# JLINK_V8_V1.net
KiCad netlist of a schematic drawn in Altium Designer
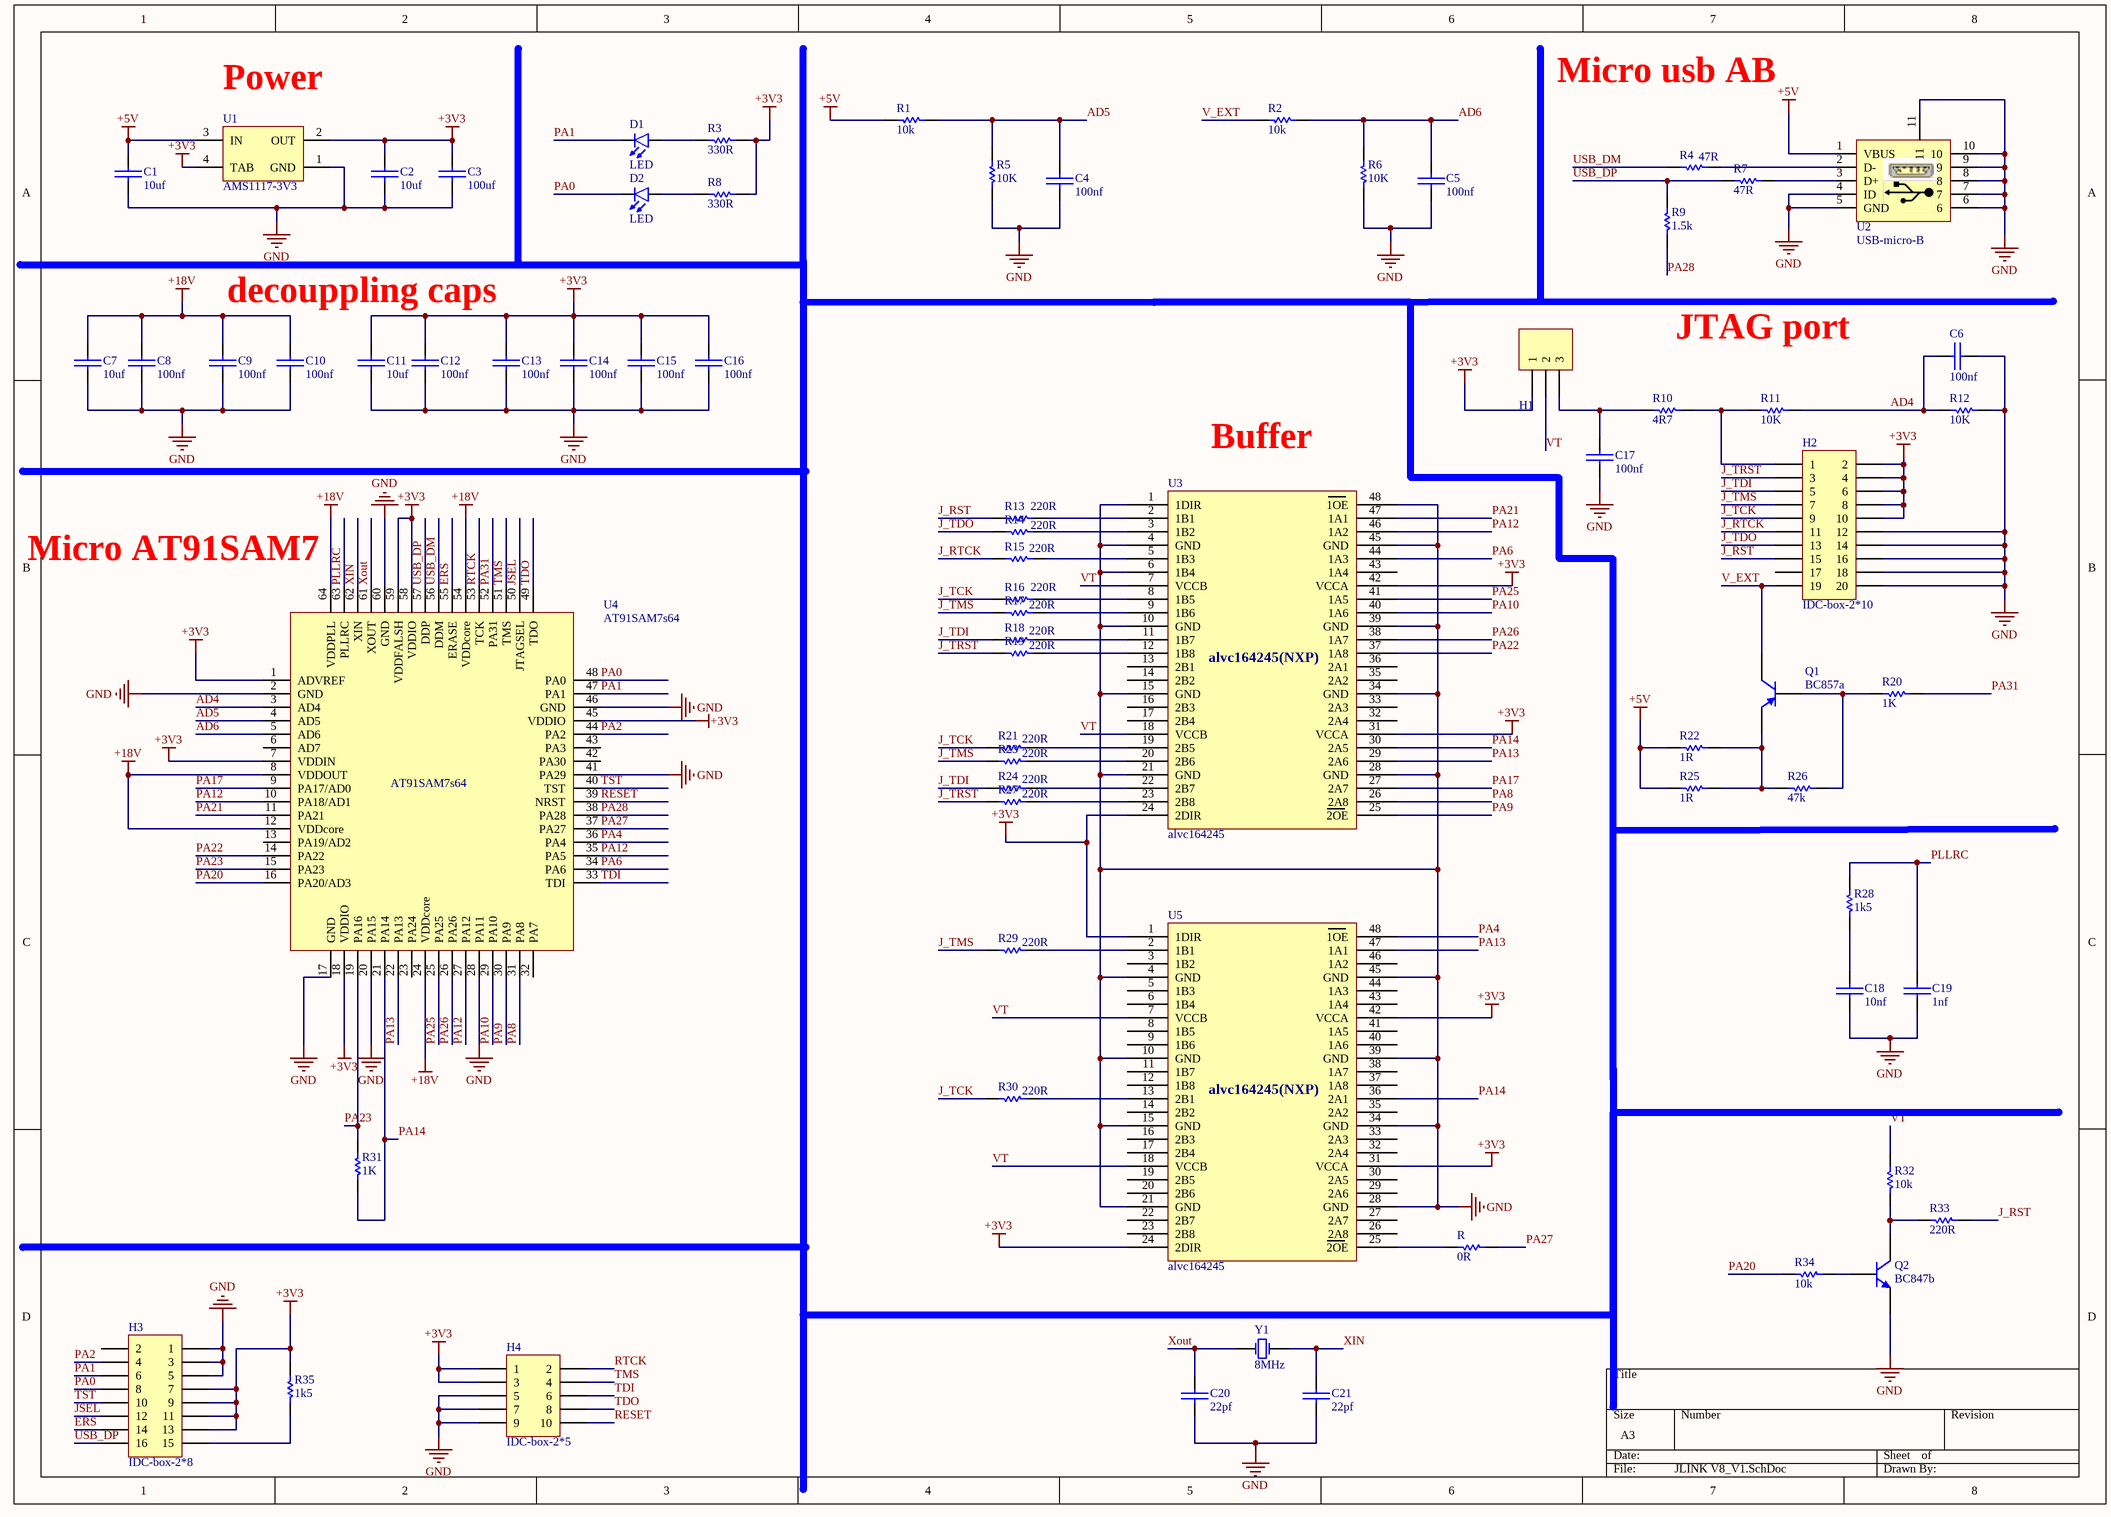
[diagram p0: JLINK V8_V1.SchDoc]

(export (version "E")
  (design (tool "Eeschema 10.0.6"))
  (components
    (comp (ref "C1")
      (value "10uf")
      (footprint "CAP-0805 - better")
      (libsource (lib "Pin_header32_Tester_V1") (part "CAP-0805"))
    )
    (comp (ref "C2")
      (value "10uf")
      (footprint "CAP-0805 - better")
      (libsource (lib "Pin_header32_Tester_V1") (part "CAP-0805"))
    )
    (comp (ref "C3")
      (value "100uf")
      (footprint "CAP-0805 - better")
      (libsource (lib "Pin_header32_Tester_V1") (part "CAP-0805"))
    )
    (comp (ref "C4")
      (value "100nf")
      (footprint "CAP-0805 - better")
      (libsource (lib "Pin_header32_Tester_V1") (part "CAP-0805"))
    )
    (comp (ref "C5")
      (value "100nf")
      (footprint "CAP-0805 - better")
      (libsource (lib "Pin_header32_Tester_V1") (part "CAP-0805"))
    )
    (comp (ref "C6")
      (value "100nf")
      (footprint "CAP-0805 - better")
      (libsource (lib "Pin_header32_Tester_V1") (part "CAP-0805"))
    )
    (comp (ref "C7")
      (value "10uf")
      (footprint "CAP-0805 - better")
      (libsource (lib "Pin_header32_Tester_V1") (part "CAP-0805"))
    )
    (comp (ref "C8")
      (value "100nf")
      (footprint "CAP-0805 - better")
      (libsource (lib "Pin_header32_Tester_V1") (part "CAP-0805"))
    )
    (comp (ref "C9")
      (value "100nf")
      (footprint "CAP-0805 - better")
      (libsource (lib "Pin_header32_Tester_V1") (part "CAP-0805"))
    )
    (comp (ref "C10")
      (value "100nf")
      (footprint "CAP-0805 - better")
      (libsource (lib "Pin_header32_Tester_V1") (part "CAP-0805"))
    )
    (comp (ref "C11")
      (value "10uf")
      (footprint "CAP-0805 - better")
      (libsource (lib "Pin_header32_Tester_V1") (part "CAP-0805"))
    )
    (comp (ref "C12")
      (value "100nf")
      (footprint "CAP-0805 - better")
      (libsource (lib "Pin_header32_Tester_V1") (part "CAP-0805"))
    )
    (comp (ref "C13")
      (value "100nf")
      (footprint "CAP-0805 - better")
      (libsource (lib "Pin_header32_Tester_V1") (part "CAP-0805"))
    )
    (comp (ref "C14")
      (value "100nf")
      (footprint "CAP-0805 - better")
      (libsource (lib "Pin_header32_Tester_V1") (part "CAP-0805"))
    )
    (comp (ref "C15")
      (value "100nf")
      (footprint "CAP-0805 - better")
      (libsource (lib "Pin_header32_Tester_V1") (part "CAP-0805"))
    )
    (comp (ref "C16")
      (value "100nf")
      (footprint "CAP-0805 - better")
      (libsource (lib "Pin_header32_Tester_V1") (part "CAP-0805"))
    )
    (comp (ref "C17")
      (value "100nf")
      (footprint "CAP-0805 - better")
      (libsource (lib "Pin_header32_Tester_V1") (part "CAP-0805"))
    )
    (comp (ref "C18")
      (value "10nf")
      (footprint "CAP-0805 - better")
      (libsource (lib "Pin_header32_Tester_V1") (part "CAP-0805"))
    )
    (comp (ref "C19")
      (value "1nf")
      (footprint "CAP-0805 - better")
      (libsource (lib "Pin_header32_Tester_V1") (part "CAP-0805"))
    )
    (comp (ref "C20")
      (value "22pf")
      (footprint "CAP-0805 - better")
      (libsource (lib "Pin_header32_Tester_V1") (part "CAP-0805"))
    )
    (comp (ref "C21")
      (value "22pf")
      (footprint "CAP-0805 - better")
      (libsource (lib "Pin_header32_Tester_V1") (part "CAP-0805"))
    )
    (comp (ref "D1")
      (value "LED")
      (footprint "LED-SMD-0805")
      (libsource (lib "Pin_header32_Tester_V1") (part "LED-SMD-RED"))
    )
    (comp (ref "D2")
      (value "LED")
      (footprint "LED-SMD-0805")
      (libsource (lib "Pin_header32_Tester_V1") (part "LED-SMD-RED"))
    )
    (comp (ref "H1")
      (value "Header 3")
      (footprint "PIN-header3(copy)")
      (description "Header, 3-Pin")
      (fields (field (name "PUBLISHER") "Altium Limited"))
      (libsource (lib "Pin_header32_Tester_V1") (part "Header 1*3"))
    )
    (comp (ref "H2")
      (value "IDC-box-2*10")
      (footprint "ICD-box_10*2")
      (libsource (lib "Pin_header32_Tester_V1") (part "Header 2*10"))
    )
    (comp (ref "H3")
      (value "IDC-box-2*8")
      (footprint "male-Header 2*8")
      (libsource (lib "Pin_header32_Tester_V1") (part "Header 2*8"))
    )
    (comp (ref "H4")
      (value "IDC-box-2*5")
      (footprint "male-Header-2*5 - duplicate")
      (description "Header, 5-Pin, Dual row")
      (fields (field (name "PUBLISHER") "Altium Limited"))
      (libsource (lib "Pin_header32_Tester_V1") (part "Header 2*5"))
    )
    (comp (ref "Q1")
      (value "BC857a")
      (footprint "sot23")
      (description "PNP Bipolar Transistor")
      (fields (field (name "PUBLISHER") "Altium Limited"))
      (libsource (lib "Pin_header32_Tester_V1") (part "PNP"))
    )
    (comp (ref "Q2")
      (value "BC847b")
      (footprint "sot23")
      (description "NPN Bipolar Transistor")
      (fields (field (name "PUBLISHER") "Altium Limited"))
      (libsource (lib "Pin_header32_Tester_V1") (part "NPN"))
    )
    (comp (ref "R")
      (value "0R")
      (footprint "Res_SMD_0805")
      (description "Resistor")
      (fields (field (name "PUBLISHER") "Altium Limited"))
      (libsource (lib "Pin_header32_Tester_V1") (part "Res"))
    )
    (comp (ref "R1")
      (value "10k")
      (footprint "Res_SMD_0805")
      (description "Resistor")
      (fields (field (name "PUBLISHER") "Altium Limited"))
      (libsource (lib "Pin_header32_Tester_V1") (part "Res"))
    )
    (comp (ref "R2")
      (value "10k")
      (footprint "Res_SMD_0805")
      (description "Resistor")
      (fields (field (name "PUBLISHER") "Altium Limited"))
      (libsource (lib "Pin_header32_Tester_V1") (part "Res"))
    )
    (comp (ref "R3")
      (value "330R")
      (footprint "Res_SMD_0805")
      (description "Resistor")
      (fields (field (name "PUBLISHER") "Altium Limited"))
      (libsource (lib "Pin_header32_Tester_V1") (part "Res"))
    )
    (comp (ref "R4")
      (value "47R")
      (footprint "Res_SMD_0805")
      (description "Resistor")
      (fields (field (name "PUBLISHER") "Altium Limited"))
      (libsource (lib "Pin_header32_Tester_V1") (part "Res"))
    )
    (comp (ref "R5")
      (value "10K")
      (footprint "Res_SMD_0805")
      (description "Resistor")
      (fields (field (name "PUBLISHER") "Altium Limited"))
      (libsource (lib "Pin_header32_Tester_V1") (part "Res"))
    )
    (comp (ref "R6")
      (value "10K")
      (footprint "Res_SMD_0805")
      (description "Resistor")
      (fields (field (name "PUBLISHER") "Altium Limited"))
      (libsource (lib "Pin_header32_Tester_V1") (part "Res"))
    )
    (comp (ref "R7")
      (value "47R")
      (footprint "Res_SMD_0805")
      (description "Resistor")
      (fields (field (name "PUBLISHER") "Altium Limited"))
      (libsource (lib "Pin_header32_Tester_V1") (part "Res"))
    )
    (comp (ref "R8")
      (value "330R")
      (footprint "Res_SMD_0805")
      (description "Resistor")
      (fields (field (name "PUBLISHER") "Altium Limited"))
      (libsource (lib "Pin_header32_Tester_V1") (part "Res"))
    )
    (comp (ref "R9")
      (value "1.5k")
      (footprint "Res_SMD_0805")
      (description "Resistor")
      (fields (field (name "PUBLISHER") "Altium Limited"))
      (libsource (lib "Pin_header32_Tester_V1") (part "Res"))
    )
    (comp (ref "R10")
      (value "4R7")
      (footprint "Res_SMD_0805")
      (description "Resistor")
      (fields (field (name "PUBLISHER") "Altium Limited"))
      (libsource (lib "Pin_header32_Tester_V1") (part "Res"))
    )
    (comp (ref "R11")
      (value "10K")
      (footprint "Res_SMD_0805")
      (description "Resistor")
      (fields (field (name "PUBLISHER") "Altium Limited"))
      (libsource (lib "Pin_header32_Tester_V1") (part "Res"))
    )
    (comp (ref "R12")
      (value "10K")
      (footprint "Res_SMD_0805")
      (description "Resistor")
      (fields (field (name "PUBLISHER") "Altium Limited"))
      (libsource (lib "Pin_header32_Tester_V1") (part "Res"))
    )
    (comp (ref "R13")
      (value "220R")
      (footprint "Res_SMD_0805")
      (description "Resistor")
      (fields (field (name "PUBLISHER") "Altium Limited"))
      (libsource (lib "Pin_header32_Tester_V1") (part "Res"))
    )
    (comp (ref "R14")
      (value "220R")
      (footprint "Res_SMD_0805")
      (description "Resistor")
      (fields (field (name "PUBLISHER") "Altium Limited"))
      (libsource (lib "Pin_header32_Tester_V1") (part "Res"))
    )
    (comp (ref "R15")
      (value "220R")
      (footprint "Res_SMD_0805")
      (description "Resistor")
      (fields (field (name "PUBLISHER") "Altium Limited"))
      (libsource (lib "Pin_header32_Tester_V1") (part "Res"))
    )
    (comp (ref "R16")
      (value "220R")
      (footprint "Res_SMD_0805")
      (description "Resistor")
      (fields (field (name "PUBLISHER") "Altium Limited"))
      (libsource (lib "Pin_header32_Tester_V1") (part "Res"))
    )
    (comp (ref "R17")
      (value "220R")
      (footprint "Res_SMD_0805")
      (description "Resistor")
      (fields (field (name "PUBLISHER") "Altium Limited"))
      (libsource (lib "Pin_header32_Tester_V1") (part "Res"))
    )
    (comp (ref "R18")
      (value "220R")
      (footprint "Res_SMD_0805")
      (description "Resistor")
      (fields (field (name "PUBLISHER") "Altium Limited"))
      (libsource (lib "Pin_header32_Tester_V1") (part "Res"))
    )
    (comp (ref "R19")
      (value "220R")
      (footprint "Res_SMD_0805")
      (description "Resistor")
      (fields (field (name "PUBLISHER") "Altium Limited"))
      (libsource (lib "Pin_header32_Tester_V1") (part "Res"))
    )
    (comp (ref "R20")
      (value "1K")
      (footprint "Res_SMD_0805")
      (description "Resistor")
      (fields (field (name "PUBLISHER") "Altium Limited"))
      (libsource (lib "Pin_header32_Tester_V1") (part "Res"))
    )
    (comp (ref "R21")
      (value "220R")
      (footprint "Res_SMD_0805")
      (description "Resistor")
      (fields (field (name "PUBLISHER") "Altium Limited"))
      (libsource (lib "Pin_header32_Tester_V1") (part "Res"))
    )
    (comp (ref "R22")
      (value "1R")
      (footprint "Res_SMD_0805")
      (description "Resistor")
      (fields (field (name "PUBLISHER") "Altium Limited"))
      (libsource (lib "Pin_header32_Tester_V1") (part "Res"))
    )
    (comp (ref "R23")
      (value "220R")
      (footprint "Res_SMD_0805")
      (description "Resistor")
      (fields (field (name "PUBLISHER") "Altium Limited"))
      (libsource (lib "Pin_header32_Tester_V1") (part "Res"))
    )
    (comp (ref "R24")
      (value "220R")
      (footprint "Res_SMD_0805")
      (description "Resistor")
      (fields (field (name "PUBLISHER") "Altium Limited"))
      (libsource (lib "Pin_header32_Tester_V1") (part "Res"))
    )
    (comp (ref "R25")
      (value "1R")
      (footprint "Res_SMD_0805")
      (description "Resistor")
      (fields (field (name "PUBLISHER") "Altium Limited"))
      (libsource (lib "Pin_header32_Tester_V1") (part "Res"))
    )
    (comp (ref "R26")
      (value "47k")
      (footprint "Res_SMD_0805")
      (description "Resistor")
      (fields (field (name "PUBLISHER") "Altium Limited"))
      (libsource (lib "Pin_header32_Tester_V1") (part "Res"))
    )
    (comp (ref "R27")
      (value "220R")
      (footprint "Res_SMD_0805")
      (description "Resistor")
      (fields (field (name "PUBLISHER") "Altium Limited"))
      (libsource (lib "Pin_header32_Tester_V1") (part "Res"))
    )
    (comp (ref "R28")
      (value "1k5")
      (footprint "Res_SMD_0805")
      (description "Resistor")
      (fields (field (name "PUBLISHER") "Altium Limited"))
      (libsource (lib "Pin_header32_Tester_V1") (part "Res"))
    )
    (comp (ref "R29")
      (value "220R")
      (footprint "Res_SMD_0805")
      (description "Resistor")
      (fields (field (name "PUBLISHER") "Altium Limited"))
      (libsource (lib "Pin_header32_Tester_V1") (part "Res"))
    )
    (comp (ref "R30")
      (value "220R")
      (footprint "Res_SMD_0805")
      (description "Resistor")
      (fields (field (name "PUBLISHER") "Altium Limited"))
      (libsource (lib "Pin_header32_Tester_V1") (part "Res"))
    )
    (comp (ref "R31")
      (value "1K")
      (footprint "Res_SMD_0805")
      (description "Resistor")
      (fields (field (name "PUBLISHER") "Altium Limited"))
      (libsource (lib "Pin_header32_Tester_V1") (part "Res"))
    )
    (comp (ref "R32")
      (value "10k")
      (footprint "Res_SMD_0805")
      (description "Resistor")
      (fields (field (name "PUBLISHER") "Altium Limited"))
      (libsource (lib "Pin_header32_Tester_V1") (part "Res"))
    )
    (comp (ref "R33")
      (value "220R")
      (footprint "Res_SMD_0805")
      (description "Resistor")
      (fields (field (name "PUBLISHER") "Altium Limited"))
      (libsource (lib "Pin_header32_Tester_V1") (part "Res"))
    )
    (comp (ref "R34")
      (value "10k")
      (footprint "Res_SMD_0805")
      (description "Resistor")
      (fields (field (name "PUBLISHER") "Altium Limited"))
      (libsource (lib "Pin_header32_Tester_V1") (part "Res"))
    )
    (comp (ref "R35")
      (value "1k5")
      (footprint "Res_SMD_0805")
      (description "Resistor")
      (fields (field (name "PUBLISHER") "Altium Limited"))
      (libsource (lib "Pin_header32_Tester_V1") (part "Res"))
    )
    (comp (ref "U1")
      (value "AMS1117-3V3")
      (footprint "AMS1117-3V3")
      (description "x.x Volt, 800mA Low-Dropout Linear Regulator, 4-pin SOT-223")
      (fields
        (field (name "PARTNUMBER") "LM1117IMP-3.3")
        (field (name "MANUFACTURER") "National Semiconductor")
        (field (name "PUBLISHER") "Altium Limited")
      )
      (libsource (lib "Pin_header32_Tester_V1") (part "AMS1117IMP-(SOT-223)"))
    )
    (comp (ref "U2")
      (value "USB-micro-B")
      (footprint "USB-micro-b")
      (libsource (lib "Pin_header32_Tester_V1") (part "USB-micro-B"))
    )
    (comp (ref "U3")
      (value "alvc164245")
      (footprint "SSOP48")
      (libsource (lib "Pin_header32_Tester_V1") (part "alvc164245(NXP)"))
    )
    (comp (ref "U4")
      (value "AT91SAM7s64")
      (footprint "LQFP-64")
      (libsource (lib "Pin_header32_Tester_V1") (part "AT91SAM7S64(LQFP)"))
    )
    (comp (ref "U5")
      (value "alvc164245")
      (footprint "SSOP48")
      (libsource (lib "Pin_header32_Tester_V1") (part "alvc164245(NXP)"))
    )
    (comp (ref "Y1")
      (value "8MHz")
      (footprint "crystall")
      (description "XTAL Crystal")
      (libsource (lib "Pin_header32_Tester_V1") (part "crystall"))
    )
  )
  (nets
    (net (code "1") (name "+3V3") (class "Default")
      (node (ref "C11") (pin "1") (pinfunction "+_1") (pintype "passive"))
      (node (ref "C12") (pin "1") (pinfunction "+_1") (pintype "passive"))
      (node (ref "C13") (pin "1") (pinfunction "+_1") (pintype "passive"))
      (node (ref "C14") (pin "1") (pinfunction "+_1") (pintype "passive"))
      (node (ref "C15") (pin "1") (pinfunction "+_1") (pintype "passive"))
      (node (ref "C16") (pin "1") (pinfunction "+_1") (pintype "passive"))
      (node (ref "C2") (pin "1") (pinfunction "+_1") (pintype "passive"))
      (node (ref "C3") (pin "1") (pinfunction "+_1") (pintype "passive"))
      (node (ref "H1") (pin "1") (pinfunction "1_1") (pintype "passive"))
      (node (ref "H2") (pin "10") (pinfunction "10_10") (pintype "passive"))
      (node (ref "H2") (pin "2") (pinfunction "2_2") (pintype "passive"))
      (node (ref "H2") (pin "4") (pinfunction "4_4") (pintype "passive"))
      (node (ref "H2") (pin "6") (pinfunction "6_6") (pintype "passive"))
      (node (ref "H2") (pin "8") (pinfunction "8_8") (pintype "passive"))
      (node (ref "H3") (pin "11") (pinfunction "11_11") (pintype "passive"))
      (node (ref "H3") (pin "13") (pinfunction "13_13") (pintype "passive"))
      (node (ref "H3") (pin "7") (pinfunction "7_7") (pintype "passive"))
      (node (ref "H3") (pin "9") (pinfunction "9_9") (pintype "passive"))
      (node (ref "H4") (pin "1") (pinfunction "1_1") (pintype "passive"))
      (node (ref "H4") (pin "3") (pinfunction "3_3") (pintype "passive"))
      (node (ref "R3") (pin "1") (pinfunction "1_1") (pintype "passive"))
      (node (ref "R35") (pin "1") (pinfunction "1_1") (pintype "passive"))
      (node (ref "R8") (pin "1") (pinfunction "1_1") (pintype "passive"))
      (node (ref "U1") (pin "2") (pinfunction "OUT_2") (pintype "power_in"))
      (node (ref "U1") (pin "4") (pinfunction "TAB_4") (pintype "power_in"))
      (node (ref "U3") (pin "24") (pinfunction "2DIR_24") (pintype "passive"))
      (node (ref "U3") (pin "31") (pinfunction "VCCA_31") (pintype "passive"))
      (node (ref "U3") (pin "42") (pinfunction "VCCA_42") (pintype "passive"))
      (node (ref "U4") (pin "1") (pinfunction "ADVREF_1") (pintype "passive"))
      (node (ref "U4") (pin "18") (pinfunction "VDDIO_18") (pintype "passive"))
      (node (ref "U4") (pin "45") (pinfunction "VDDIO_45") (pintype "passive"))
      (node (ref "U4") (pin "58") (pinfunction "VDDIO_58") (pintype "passive"))
      (node (ref "U4") (pin "59") (pinfunction "VDDFALSH_59") (pintype "passive"))
      (node (ref "U4") (pin "7") (pinfunction "VDDIN_7") (pintype "passive"))
      (node (ref "U5") (pin "1") (pinfunction "1DIR_1") (pintype "passive"))
      (node (ref "U5") (pin "24") (pinfunction "2DIR_24") (pintype "passive"))
      (node (ref "U5") (pin "31") (pinfunction "VCCA_31") (pintype "passive"))
      (node (ref "U5") (pin "42") (pinfunction "VCCA_42") (pintype "passive"))
    )
    (net (code "2") (name "+5V") (class "Default")
      (node (ref "C1") (pin "1") (pinfunction "+_1") (pintype "passive"))
      (node (ref "R1") (pin "2") (pinfunction "2_2") (pintype "passive"))
      (node (ref "R22") (pin "2") (pinfunction "2_2") (pintype "passive"))
      (node (ref "R25") (pin "2") (pinfunction "2_2") (pintype "passive"))
      (node (ref "U1") (pin "3") (pinfunction "IN_3") (pintype "power_in"))
      (node (ref "U2") (pin "1") (pinfunction "VBUS_1") (pintype "power_in"))
    )
    (net (code "3") (name "+18V") (class "Default")
      (node (ref "C10") (pin "1") (pinfunction "+_1") (pintype "passive"))
      (node (ref "C7") (pin "1") (pinfunction "+_1") (pintype "passive"))
      (node (ref "C8") (pin "1") (pinfunction "+_1") (pintype "passive"))
      (node (ref "C9") (pin "1") (pinfunction "+_1") (pintype "passive"))
      (node (ref "U4") (pin "12") (pinfunction "VDDcore_12") (pintype "passive"))
      (node (ref "U4") (pin "24") (pinfunction "VDDcore_24") (pintype "passive"))
      (node (ref "U4") (pin "54") (pinfunction "VDDcore_54") (pintype "passive"))
      (node (ref "U4") (pin "64") (pinfunction "VDDPLL_64") (pintype "passive"))
      (node (ref "U4") (pin "8") (pinfunction "VDDOUT_8") (pintype "passive"))
    )
    (net (code "4") (name "/AD4") (class "Default")
      (node (ref "C6") (pin "1") (pinfunction "+_1") (pintype "passive"))
      (node (ref "R11") (pin "2") (pinfunction "2_2") (pintype "passive"))
      (node (ref "R12") (pin "1") (pinfunction "1_1") (pintype "passive"))
      (node (ref "U4") (pin "3") (pinfunction "AD4_3") (pintype "passive"))
    )
    (net (code "5") (name "/AD5") (class "Default")
      (node (ref "C4") (pin "1") (pinfunction "+_1") (pintype "passive"))
      (node (ref "R1") (pin "1") (pinfunction "1_1") (pintype "passive"))
      (node (ref "R5") (pin "1") (pinfunction "1_1") (pintype "passive"))
      (node (ref "U4") (pin "4") (pinfunction "AD5_4") (pintype "passive"))
    )
    (net (code "6") (name "/AD6") (class "Default")
      (node (ref "C5") (pin "1") (pinfunction "+_1") (pintype "passive"))
      (node (ref "R2") (pin "1") (pinfunction "1_1") (pintype "passive"))
      (node (ref "R6") (pin "1") (pinfunction "1_1") (pintype "passive"))
      (node (ref "U4") (pin "5") (pinfunction "AD6_5") (pintype "passive"))
    )
    (net (code "7") (name "/ERS") (class "Default")
      (node (ref "H3") (pin "14") (pinfunction "14_14") (pintype "passive"))
      (node (ref "U4") (pin "55") (pinfunction "ERASE_55") (pintype "passive"))
    )
    (net (code "8") (name "/JSEL") (class "Default")
      (node (ref "H3") (pin "12") (pinfunction "12_12") (pintype "passive"))
      (node (ref "U4") (pin "50") (pinfunction "JTAGSEL_50") (pintype "passive"))
    )
    (net (code "9") (name "/J_RST") (class "Default")
      (node (ref "H2") (pin "15") (pinfunction "15_15") (pintype "passive"))
      (node (ref "R13") (pin "2") (pinfunction "2_2") (pintype "passive"))
      (node (ref "R33") (pin "1") (pinfunction "1_1") (pintype "passive"))
    )
    (net (code "10") (name "/J_RTCK") (class "Default")
      (node (ref "H2") (pin "11") (pinfunction "11_11") (pintype "passive"))
      (node (ref "R15") (pin "2") (pinfunction "2_2") (pintype "passive"))
    )
    (net (code "11") (name "/J_TCK") (class "Default")
      (node (ref "H2") (pin "9") (pinfunction "9_9") (pintype "passive"))
      (node (ref "R16") (pin "2") (pinfunction "2_2") (pintype "passive"))
      (node (ref "R21") (pin "2") (pinfunction "2_2") (pintype "passive"))
      (node (ref "R30") (pin "2") (pinfunction "2_2") (pintype "passive"))
    )
    (net (code "12") (name "/J_TDI") (class "Default")
      (node (ref "H2") (pin "5") (pinfunction "5_5") (pintype "passive"))
      (node (ref "R18") (pin "2") (pinfunction "2_2") (pintype "passive"))
      (node (ref "R24") (pin "2") (pinfunction "2_2") (pintype "passive"))
    )
    (net (code "13") (name "/J_TDO") (class "Default")
      (node (ref "H2") (pin "13") (pinfunction "13_13") (pintype "passive"))
      (node (ref "R14") (pin "2") (pinfunction "2_2") (pintype "passive"))
    )
    (net (code "14") (name "/J_TMS") (class "Default")
      (node (ref "H2") (pin "7") (pinfunction "7_7") (pintype "passive"))
      (node (ref "R17") (pin "2") (pinfunction "2_2") (pintype "passive"))
      (node (ref "R23") (pin "2") (pinfunction "2_2") (pintype "passive"))
      (node (ref "R29") (pin "2") (pinfunction "2_2") (pintype "passive"))
    )
    (net (code "15") (name "/J_TRST") (class "Default")
      (node (ref "H2") (pin "3") (pinfunction "3_3") (pintype "passive"))
      (node (ref "R19") (pin "2") (pinfunction "2_2") (pintype "passive"))
      (node (ref "R27") (pin "2") (pinfunction "2_2") (pintype "passive"))
    )
    (net (code "16") (name "/PA0") (class "Default")
      (node (ref "D2") (pin "2") (pinfunction "K_2") (pintype "passive"))
      (node (ref "H3") (pin "8") (pinfunction "8_8") (pintype "passive"))
      (node (ref "U4") (pin "48") (pinfunction "PA0_48") (pintype "passive"))
    )
    (net (code "17") (name "/PA1") (class "Default")
      (node (ref "D1") (pin "2") (pinfunction "K_2") (pintype "passive"))
      (node (ref "H3") (pin "6") (pinfunction "6_6") (pintype "passive"))
      (node (ref "U4") (pin "47") (pinfunction "PA1_47") (pintype "passive"))
    )
    (net (code "18") (name "/PA2") (class "Default")
      (node (ref "H3") (pin "4") (pinfunction "4_4") (pintype "passive"))
      (node (ref "U4") (pin "44") (pinfunction "PA2_44") (pintype "passive"))
    )
    (net (code "19") (name "/PA4") (class "Default")
      (node (ref "U4") (pin "36") (pinfunction "PA4_36") (pintype "passive"))
      (node (ref "U5") (pin "48") (pinfunction "1OE_48") (pintype "passive"))
    )
    (net (code "20") (name "/PA6") (class "Default")
      (node (ref "U3") (pin "44") (pinfunction "1A3_44") (pintype "passive"))
      (node (ref "U4") (pin "34") (pinfunction "PA6_34") (pintype "passive"))
    )
    (net (code "21") (name "/PA8") (class "Default")
      (node (ref "U3") (pin "26") (pinfunction "2A8_26") (pintype "passive"))
      (node (ref "U4") (pin "31") (pinfunction "PA8_31") (pintype "passive"))
    )
    (net (code "22") (name "/PA9") (class "Default")
      (node (ref "U3") (pin "25") (pinfunction "2OE_25") (pintype "passive"))
      (node (ref "U4") (pin "30") (pinfunction "PA9_30") (pintype "passive"))
    )
    (net (code "23") (name "/PA10") (class "Default")
      (node (ref "U3") (pin "40") (pinfunction "1A6_40") (pintype "passive"))
      (node (ref "U4") (pin "29") (pinfunction "PA10_29") (pintype "passive"))
    )
    (net (code "24") (name "/PA12") (class "Default")
      (node (ref "U3") (pin "46") (pinfunction "1A2_46") (pintype "passive"))
      (node (ref "U4") (pin "10") (pinfunction "PA18/AD1_10") (pintype "passive"))
      (node (ref "U4") (pin "27") (pinfunction "PA12_27") (pintype "passive"))
      (node (ref "U4") (pin "35") (pinfunction "PA5_35") (pintype "passive"))
    )
    (net (code "25") (name "/PA13") (class "Default")
      (node (ref "U3") (pin "29") (pinfunction "2A6_29") (pintype "passive"))
      (node (ref "U4") (pin "22") (pinfunction "PA13_22") (pintype "passive"))
      (node (ref "U5") (pin "47") (pinfunction "1A1_47") (pintype "passive"))
    )
    (net (code "26") (name "/PA14") (class "Default")
      (node (ref "R31") (pin "2") (pinfunction "2_2") (pintype "passive"))
      (node (ref "U3") (pin "30") (pinfunction "2A5_30") (pintype "passive"))
      (node (ref "U4") (pin "21") (pinfunction "PA14_21") (pintype "passive"))
      (node (ref "U5") (pin "36") (pinfunction "2A1_36") (pintype "passive"))
    )
    (net (code "27") (name "/PA17") (class "Default")
      (node (ref "U3") (pin "27") (pinfunction "2A7_27") (pintype "passive"))
      (node (ref "U4") (pin "9") (pinfunction "PA17/AD0_9") (pintype "passive"))
    )
    (net (code "28") (name "/PA20") (class "Default")
      (node (ref "R34") (pin "2") (pinfunction "2_2") (pintype "passive"))
      (node (ref "U4") (pin "16") (pinfunction "PA20/AD3_16") (pintype "passive"))
    )
    (net (code "29") (name "/PA21") (class "Default")
      (node (ref "U3") (pin "47") (pinfunction "1A1_47") (pintype "passive"))
      (node (ref "U4") (pin "11") (pinfunction "PA21_11") (pintype "passive"))
    )
    (net (code "30") (name "/PA22") (class "Default")
      (node (ref "U3") (pin "37") (pinfunction "1A8_37") (pintype "passive"))
      (node (ref "U4") (pin "14") (pinfunction "PA22_14") (pintype "passive"))
    )
    (net (code "31") (name "/PA23") (class "Default")
      (node (ref "R31") (pin "1") (pinfunction "1_1") (pintype "passive"))
      (node (ref "U4") (pin "15") (pinfunction "PA23_15") (pintype "passive"))
      (node (ref "U4") (pin "19") (pinfunction "PA16_19") (pintype "passive"))
    )
    (net (code "32") (name "/PA25") (class "Default")
      (node (ref "U3") (pin "41") (pinfunction "1A5_41") (pintype "passive"))
      (node (ref "U4") (pin "25") (pinfunction "PA25_25") (pintype "passive"))
    )
    (net (code "33") (name "/PA26") (class "Default")
      (node (ref "U3") (pin "38") (pinfunction "1A7_38") (pintype "passive"))
      (node (ref "U4") (pin "26") (pinfunction "PA26_26") (pintype "passive"))
    )
    (net (code "34") (name "/PA27") (class "Default")
      (node (ref "R") (pin "1") (pinfunction "1_1") (pintype "passive"))
      (node (ref "U4") (pin "37") (pinfunction "PA27_37") (pintype "passive"))
    )
    (net (code "35") (name "/PA28") (class "Default")
      (node (ref "R9") (pin "2") (pinfunction "2_2") (pintype "passive"))
      (node (ref "U4") (pin "38") (pinfunction "PA28_38") (pintype "passive"))
    )
    (net (code "36") (name "/PA31") (class "Default")
      (node (ref "R20") (pin "1") (pinfunction "1_1") (pintype "passive"))
      (node (ref "U4") (pin "52") (pinfunction "PA31_52") (pintype "passive"))
    )
    (net (code "37") (name "/PLLRC") (class "Default")
      (node (ref "C19") (pin "1") (pinfunction "+_1") (pintype "passive"))
      (node (ref "R28") (pin "1") (pinfunction "1_1") (pintype "passive"))
      (node (ref "U4") (pin "63") (pinfunction "PLLRC_63") (pintype "passive"))
    )
    (net (code "38") (name "/RESET") (class "Default")
      (node (ref "H4") (pin "10") (pinfunction "10_10") (pintype "passive"))
      (node (ref "U4") (pin "39") (pinfunction "NRST_39") (pintype "passive"))
    )
    (net (code "39") (name "/RTCK") (class "Default")
      (node (ref "H4") (pin "2") (pinfunction "2_2") (pintype "passive"))
      (node (ref "U4") (pin "53") (pinfunction "TCK_53") (pintype "passive"))
    )
    (net (code "40") (name "/TDI") (class "Default")
      (node (ref "H4") (pin "6") (pinfunction "6_6") (pintype "passive"))
      (node (ref "U4") (pin "33") (pinfunction "TDI_33") (pintype "passive"))
    )
    (net (code "41") (name "/TDO") (class "Default")
      (node (ref "H4") (pin "8") (pinfunction "8_8") (pintype "passive"))
      (node (ref "U4") (pin "49") (pinfunction "TDO_49") (pintype "passive"))
    )
    (net (code "42") (name "/TMS") (class "Default")
      (node (ref "H4") (pin "4") (pinfunction "4_4") (pintype "passive"))
      (node (ref "U4") (pin "51") (pinfunction "TMS_51") (pintype "passive"))
    )
    (net (code "43") (name "/TST") (class "Default")
      (node (ref "H3") (pin "10") (pinfunction "10_10") (pintype "passive"))
      (node (ref "U4") (pin "40") (pinfunction "TST_40") (pintype "passive"))
    )
    (net (code "44") (name "/USB_DM") (class "Default")
      (node (ref "R4") (pin "2") (pinfunction "2_2") (pintype "passive"))
      (node (ref "U4") (pin "56") (pinfunction "DDM_56") (pintype "passive"))
    )
    (net (code "45") (name "/USB_DP") (class "Default")
      (node (ref "H3") (pin "16") (pinfunction "16_16") (pintype "passive"))
      (node (ref "R7") (pin "2") (pinfunction "2_2") (pintype "passive"))
      (node (ref "R9") (pin "1") (pinfunction "1_1") (pintype "passive"))
      (node (ref "U4") (pin "57") (pinfunction "DDP_57") (pintype "passive"))
    )
    (net (code "46") (name "/VT") (class "Default")
      (node (ref "H1") (pin "2") (pinfunction "2_2") (pintype "passive"))
      (node (ref "R32") (pin "1") (pinfunction "1_1") (pintype "passive"))
      (node (ref "U3") (pin "18") (pinfunction "VCCB_18") (pintype "passive"))
      (node (ref "U3") (pin "7") (pinfunction "VCCB_7") (pintype "passive"))
      (node (ref "U5") (pin "18") (pinfunction "VCCB_18") (pintype "passive"))
      (node (ref "U5") (pin "7") (pinfunction "VCCB_7") (pintype "passive"))
    )
    (net (code "47") (name "/V_EXT") (class "Default")
      (node (ref "H2") (pin "19") (pinfunction "19_19") (pintype "passive"))
      (node (ref "Q1") (pin "3") (pinfunction "C_3") (pintype "passive"))
      (node (ref "R2") (pin "2") (pinfunction "2_2") (pintype "passive"))
    )
    (net (code "48") (name "/XIN") (class "Default")
      (node (ref "C21") (pin "1") (pinfunction "+_1") (pintype "passive"))
      (node (ref "U4") (pin "62") (pinfunction "XIN_62") (pintype "passive"))
      (node (ref "Y1") (pin "1") (pinfunction "OSC1_1") (pintype "passive"))
    )
    (net (code "49") (name "/Xout") (class "Default")
      (node (ref "C20") (pin "1") (pinfunction "+_1") (pintype "passive"))
      (node (ref "U4") (pin "61") (pinfunction "XOUT_61") (pintype "passive"))
      (node (ref "Y1") (pin "2") (pinfunction "OSC2_2") (pintype "passive"))
    )
    (net (code "50") (name "GND") (class "Default")
      (node (ref "C1") (pin "2") (pinfunction "-_2") (pintype "passive"))
      (node (ref "C10") (pin "2") (pinfunction "-_2") (pintype "passive"))
      (node (ref "C11") (pin "2") (pinfunction "-_2") (pintype "passive"))
      (node (ref "C12") (pin "2") (pinfunction "-_2") (pintype "passive"))
      (node (ref "C13") (pin "2") (pinfunction "-_2") (pintype "passive"))
      (node (ref "C14") (pin "2") (pinfunction "-_2") (pintype "passive"))
      (node (ref "C15") (pin "2") (pinfunction "-_2") (pintype "passive"))
      (node (ref "C16") (pin "2") (pinfunction "-_2") (pintype "passive"))
      (node (ref "C17") (pin "2") (pinfunction "-_2") (pintype "passive"))
      (node (ref "C18") (pin "2") (pinfunction "-_2") (pintype "passive"))
      (node (ref "C19") (pin "2") (pinfunction "-_2") (pintype "passive"))
      (node (ref "C2") (pin "2") (pinfunction "-_2") (pintype "passive"))
      (node (ref "C20") (pin "2") (pinfunction "-_2") (pintype "passive"))
      (node (ref "C21") (pin "2") (pinfunction "-_2") (pintype "passive"))
      (node (ref "C3") (pin "2") (pinfunction "-_2") (pintype "passive"))
      (node (ref "C4") (pin "2") (pinfunction "-_2") (pintype "passive"))
      (node (ref "C5") (pin "2") (pinfunction "-_2") (pintype "passive"))
      (node (ref "C6") (pin "2") (pinfunction "-_2") (pintype "passive"))
      (node (ref "C7") (pin "2") (pinfunction "-_2") (pintype "passive"))
      (node (ref "C8") (pin "2") (pinfunction "-_2") (pintype "passive"))
      (node (ref "C9") (pin "2") (pinfunction "-_2") (pintype "passive"))
      (node (ref "H2") (pin "12") (pinfunction "12_12") (pintype "passive"))
      (node (ref "H2") (pin "14") (pinfunction "14_14") (pintype "passive"))
      (node (ref "H2") (pin "16") (pinfunction "16_16") (pintype "passive"))
      (node (ref "H2") (pin "18") (pinfunction "18_18") (pintype "passive"))
      (node (ref "H2") (pin "20") (pinfunction "20_20") (pintype "passive"))
      (node (ref "H3") (pin "1") (pinfunction "1_1") (pintype "passive"))
      (node (ref "H3") (pin "3") (pinfunction "3_3") (pintype "passive"))
      (node (ref "H3") (pin "5") (pinfunction "5_5") (pintype "passive"))
      (node (ref "H4") (pin "5") (pinfunction "5_5") (pintype "passive"))
      (node (ref "H4") (pin "7") (pinfunction "7_7") (pintype "passive"))
      (node (ref "H4") (pin "9") (pinfunction "9_9") (pintype "passive"))
      (node (ref "Q2") (pin "2") (pinfunction "E_2") (pintype "passive"))
      (node (ref "R12") (pin "2") (pinfunction "2_2") (pintype "passive"))
      (node (ref "R5") (pin "2") (pinfunction "2_2") (pintype "passive"))
      (node (ref "R6") (pin "2") (pinfunction "2_2") (pintype "passive"))
      (node (ref "U1") (pin "1") (pinfunction "GND_1") (pintype "power_in"))
      (node (ref "U2") (pin "10") (pinfunction "10_10") (pintype "passive"))
      (node (ref "U2") (pin "11") (pinfunction "11_11") (pintype "passive"))
      (node (ref "U2") (pin "4") (pinfunction "ID_4") (pintype "power_in"))
      (node (ref "U2") (pin "5") (pinfunction "GND_5") (pintype "power_in"))
      (node (ref "U2") (pin "6") (pinfunction "6_6") (pintype "passive"))
      (node (ref "U2") (pin "7") (pinfunction "7_7") (pintype "passive"))
      (node (ref "U2") (pin "8") (pinfunction "8_8") (pintype "passive"))
      (node (ref "U2") (pin "9") (pinfunction "9_9") (pintype "passive"))
      (node (ref "U3") (pin "1") (pinfunction "1DIR_1") (pintype "passive"))
      (node (ref "U3") (pin "10") (pinfunction "GND_10") (pintype "passive"))
      (node (ref "U3") (pin "15") (pinfunction "GND_15") (pintype "passive"))
      (node (ref "U3") (pin "21") (pinfunction "GND_21") (pintype "passive"))
      (node (ref "U3") (pin "28") (pinfunction "GND_28") (pintype "passive"))
      (node (ref "U3") (pin "34") (pinfunction "GND_34") (pintype "passive"))
      (node (ref "U3") (pin "39") (pinfunction "GND_39") (pintype "passive"))
      (node (ref "U3") (pin "4") (pinfunction "GND_4") (pintype "passive"))
      (node (ref "U3") (pin "45") (pinfunction "GND_45") (pintype "passive"))
      (node (ref "U3") (pin "48") (pinfunction "1OE_48") (pintype "passive"))
      (node (ref "U3") (pin "6") (pinfunction "1B4_6") (pintype "passive"))
      (node (ref "U4") (pin "17") (pinfunction "GND_17") (pintype "passive"))
      (node (ref "U4") (pin "2") (pinfunction "GND_2") (pintype "passive"))
      (node (ref "U4") (pin "20") (pinfunction "PA15_20") (pintype "passive"))
      (node (ref "U4") (pin "28") (pinfunction "PA11_28") (pintype "passive"))
      (node (ref "U4") (pin "41") (pinfunction "PA29_41") (pintype "passive"))
      (node (ref "U4") (pin "46") (pinfunction "GND_46") (pintype "passive"))
      (node (ref "U4") (pin "60") (pinfunction "GND_60") (pintype "passive"))
      (node (ref "U5") (pin "10") (pinfunction "GND_10") (pintype "passive"))
      (node (ref "U5") (pin "15") (pinfunction "GND_15") (pintype "passive"))
      (node (ref "U5") (pin "21") (pinfunction "GND_21") (pintype "passive"))
      (node (ref "U5") (pin "28") (pinfunction "GND_28") (pintype "passive"))
      (node (ref "U5") (pin "34") (pinfunction "GND_34") (pintype "passive"))
      (node (ref "U5") (pin "39") (pinfunction "GND_39") (pintype "passive"))
      (node (ref "U5") (pin "4") (pinfunction "GND_4") (pintype "passive"))
      (node (ref "U5") (pin "45") (pinfunction "GND_45") (pintype "passive"))
    )
    (net (code "51") (name "Net-(C17-+)") (class "Default")
      (node (ref "C17") (pin "1") (pinfunction "+_1") (pintype "passive"))
      (node (ref "H1") (pin "3") (pinfunction "3_3") (pintype "passive"))
      (node (ref "R10") (pin "2") (pinfunction "2_2") (pintype "passive"))
    )
    (net (code "52") (name "Net-(C18-+)") (class "Default")
      (node (ref "C18") (pin "1") (pinfunction "+_1") (pintype "passive"))
      (node (ref "R28") (pin "2") (pinfunction "2_2") (pintype "passive"))
    )
    (net (code "53") (name "Net-(D1-A)") (class "Default")
      (node (ref "D1") (pin "1") (pinfunction "A_1") (pintype "passive"))
      (node (ref "R3") (pin "2") (pinfunction "2_2") (pintype "passive"))
    )
    (net (code "54") (name "Net-(D2-A)") (class "Default")
      (node (ref "D2") (pin "1") (pinfunction "A_1") (pintype "passive"))
      (node (ref "R8") (pin "2") (pinfunction "2_2") (pintype "passive"))
    )
    (net (code "55") (name "Net-(H2-Pad1)") (class "Default")
      (node (ref "H2") (pin "1") (pinfunction "1_1") (pintype "passive"))
      (node (ref "R10") (pin "1") (pinfunction "1_1") (pintype "passive"))
      (node (ref "R11") (pin "1") (pinfunction "1_1") (pintype "passive"))
    )
    (net (code "56") (name "Net-(H3-Pad15)") (class "Default")
      (node (ref "H3") (pin "15") (pinfunction "15_15") (pintype "passive"))
      (node (ref "R35") (pin "2") (pinfunction "2_2") (pintype "passive"))
    )
    (net (code "57") (name "Net-(Q1-B)") (class "Default")
      (node (ref "Q1") (pin "1") (pinfunction "B_1") (pintype "passive"))
      (node (ref "R20") (pin "2") (pinfunction "2_2") (pintype "passive"))
      (node (ref "R26") (pin "1") (pinfunction "1_1") (pintype "passive"))
    )
    (net (code "58") (name "Net-(Q1-E)") (class "Default")
      (node (ref "Q1") (pin "2") (pinfunction "E_2") (pintype "passive"))
      (node (ref "R22") (pin "1") (pinfunction "1_1") (pintype "passive"))
      (node (ref "R25") (pin "1") (pinfunction "1_1") (pintype "passive"))
      (node (ref "R26") (pin "2") (pinfunction "2_2") (pintype "passive"))
    )
    (net (code "59") (name "Net-(Q2-B)") (class "Default")
      (node (ref "Q2") (pin "1") (pinfunction "B_1") (pintype "passive"))
      (node (ref "R34") (pin "1") (pinfunction "1_1") (pintype "passive"))
    )
    (net (code "60") (name "Net-(Q2-C)") (class "Default")
      (node (ref "Q2") (pin "3") (pinfunction "C_3") (pintype "passive"))
      (node (ref "R32") (pin "2") (pinfunction "2_2") (pintype "passive"))
      (node (ref "R33") (pin "2") (pinfunction "2_2") (pintype "passive"))
    )
    (net (code "61") (name "Net-(U2-D+)") (class "Default")
      (node (ref "R7") (pin "1") (pinfunction "1_1") (pintype "passive"))
      (node (ref "U2") (pin "3") (pinfunction "D+_3") (pintype "passive"))
    )
    (net (code "62") (name "Net-(U2-D-)") (class "Default")
      (node (ref "R4") (pin "1") (pinfunction "1_1") (pintype "passive"))
      (node (ref "U2") (pin "2") (pinfunction "D-_2") (pintype "passive"))
    )
    (net (code "63") (name "Net-(U3-1B1)") (class "Default")
      (node (ref "R13") (pin "1") (pinfunction "1_1") (pintype "passive"))
      (node (ref "U3") (pin "2") (pinfunction "1B1_2") (pintype "passive"))
    )
    (net (code "64") (name "Net-(U3-1B2)") (class "Default")
      (node (ref "R14") (pin "1") (pinfunction "1_1") (pintype "passive"))
      (node (ref "U3") (pin "3") (pinfunction "1B2_3") (pintype "passive"))
    )
    (net (code "65") (name "Net-(U3-1B3)") (class "Default")
      (node (ref "R15") (pin "1") (pinfunction "1_1") (pintype "passive"))
      (node (ref "U3") (pin "5") (pinfunction "1B3_5") (pintype "passive"))
    )
    (net (code "66") (name "Net-(U3-1B5)") (class "Default")
      (node (ref "R16") (pin "1") (pinfunction "1_1") (pintype "passive"))
      (node (ref "U3") (pin "8") (pinfunction "1B5_8") (pintype "passive"))
    )
    (net (code "67") (name "Net-(U3-1B6)") (class "Default")
      (node (ref "R17") (pin "1") (pinfunction "1_1") (pintype "passive"))
      (node (ref "U3") (pin "9") (pinfunction "1B6_9") (pintype "passive"))
    )
    (net (code "68") (name "Net-(U3-1B7)") (class "Default")
      (node (ref "R18") (pin "1") (pinfunction "1_1") (pintype "passive"))
      (node (ref "U3") (pin "11") (pinfunction "1B7_11") (pintype "passive"))
    )
    (net (code "69") (name "Net-(U3-1B8)") (class "Default")
      (node (ref "R19") (pin "1") (pinfunction "1_1") (pintype "passive"))
      (node (ref "U3") (pin "12") (pinfunction "1B8_12") (pintype "passive"))
    )
    (net (code "70") (name "Net-(U3-2B5)") (class "Default")
      (node (ref "R21") (pin "1") (pinfunction "1_1") (pintype "passive"))
      (node (ref "U3") (pin "19") (pinfunction "2B5_19") (pintype "passive"))
    )
    (net (code "71") (name "Net-(U3-2B6)") (class "Default")
      (node (ref "R23") (pin "1") (pinfunction "1_1") (pintype "passive"))
      (node (ref "U3") (pin "20") (pinfunction "2B6_20") (pintype "passive"))
    )
    (net (code "72") (name "Net-(U3-2B7)") (class "Default")
      (node (ref "R24") (pin "1") (pinfunction "1_1") (pintype "passive"))
      (node (ref "U3") (pin "22") (pinfunction "2B7_22") (pintype "passive"))
    )
    (net (code "73") (name "Net-(U3-2B8)") (class "Default")
      (node (ref "R27") (pin "1") (pinfunction "1_1") (pintype "passive"))
      (node (ref "U3") (pin "23") (pinfunction "2B8_23") (pintype "passive"))
    )
    (net (code "74") (name "Net-(U5-1B1)") (class "Default")
      (node (ref "R29") (pin "1") (pinfunction "1_1") (pintype "passive"))
      (node (ref "U5") (pin "2") (pinfunction "1B1_2") (pintype "passive"))
    )
    (net (code "75") (name "Net-(U5-2B1)") (class "Default")
      (node (ref "R30") (pin "1") (pinfunction "1_1") (pintype "passive"))
      (node (ref "U5") (pin "13") (pinfunction "2B1_13") (pintype "passive"))
    )
    (net (code "76") (name "Net-(U5-2OE)") (class "Default")
      (node (ref "R") (pin "2") (pinfunction "2_2") (pintype "passive"))
      (node (ref "U5") (pin "25") (pinfunction "2OE_25") (pintype "passive"))
    )
    (net (code "77") (name "unconnected-(H2-Pad17)") (class "Default")
      (node (ref "H2") (pin "17") (pinfunction "17_17") (pintype "passive"))
    )
    (net (code "78") (name "unconnected-(H3-Pad2)") (class "Default")
      (node (ref "H3") (pin "2") (pinfunction "2_2") (pintype "passive"))
    )
    (net (code "79") (name "unconnected-(U3-1A4-Pad43)") (class "Default")
      (node (ref "U3") (pin "43") (pinfunction "1A4_43") (pintype "passive"))
    )
    (net (code "80") (name "unconnected-(U3-2A1-Pad36)") (class "Default")
      (node (ref "U3") (pin "36") (pinfunction "2A1_36") (pintype "passive"))
    )
    (net (code "81") (name "unconnected-(U3-2A2-Pad35)") (class "Default")
      (node (ref "U3") (pin "35") (pinfunction "2A2_35") (pintype "passive"))
    )
    (net (code "82") (name "unconnected-(U3-2A3-Pad33)") (class "Default")
      (node (ref "U3") (pin "33") (pinfunction "2A3_33") (pintype "passive"))
    )
    (net (code "83") (name "unconnected-(U3-2A4-Pad32)") (class "Default")
      (node (ref "U3") (pin "32") (pinfunction "2A4_32") (pintype "passive"))
    )
    (net (code "84") (name "unconnected-(U3-2B1-Pad13)") (class "Default")
      (node (ref "U3") (pin "13") (pinfunction "2B1_13") (pintype "passive"))
    )
    (net (code "85") (name "unconnected-(U3-2B2-Pad14)") (class "Default")
      (node (ref "U3") (pin "14") (pinfunction "2B2_14") (pintype "passive"))
    )
    (net (code "86") (name "unconnected-(U3-2B3-Pad16)") (class "Default")
      (node (ref "U3") (pin "16") (pinfunction "2B3_16") (pintype "passive"))
    )
    (net (code "87") (name "unconnected-(U3-2B4-Pad17)") (class "Default")
      (node (ref "U3") (pin "17") (pinfunction "2B4_17") (pintype "passive"))
    )
    (net (code "88") (name "unconnected-(U4-AD7-Pad6)") (class "Default")
      (node (ref "U4") (pin "6") (pinfunction "AD7_6") (pintype "passive"))
    )
    (net (code "89") (name "unconnected-(U4-PA3-Pad43)") (class "Default")
      (node (ref "U4") (pin "43") (pinfunction "PA3_43") (pintype "passive"))
    )
    (net (code "90") (name "unconnected-(U4-PA7-Pad32)") (class "Default")
      (node (ref "U4") (pin "32") (pinfunction "PA7_32") (pintype "passive"))
    )
    (net (code "91") (name "unconnected-(U4-PA19{slash}AD2-Pad13)") (class "Default")
      (node (ref "U4") (pin "13") (pinfunction "PA19/AD2_13") (pintype "passive"))
    )
    (net (code "92") (name "unconnected-(U4-PA24-Pad23)") (class "Default")
      (node (ref "U4") (pin "23") (pinfunction "PA24_23") (pintype "passive"))
    )
    (net (code "93") (name "unconnected-(U4-PA30-Pad42)") (class "Default")
      (node (ref "U4") (pin "42") (pinfunction "PA30_42") (pintype "passive"))
    )
    (net (code "94") (name "unconnected-(U5-1A2-Pad46)") (class "Default")
      (node (ref "U5") (pin "46") (pinfunction "1A2_46") (pintype "passive"))
    )
    (net (code "95") (name "unconnected-(U5-1A3-Pad44)") (class "Default")
      (node (ref "U5") (pin "44") (pinfunction "1A3_44") (pintype "passive"))
    )
    (net (code "96") (name "unconnected-(U5-1A4-Pad43)") (class "Default")
      (node (ref "U5") (pin "43") (pinfunction "1A4_43") (pintype "passive"))
    )
    (net (code "97") (name "unconnected-(U5-1A5-Pad41)") (class "Default")
      (node (ref "U5") (pin "41") (pinfunction "1A5_41") (pintype "passive"))
    )
    (net (code "98") (name "unconnected-(U5-1A6-Pad40)") (class "Default")
      (node (ref "U5") (pin "40") (pinfunction "1A6_40") (pintype "passive"))
    )
    (net (code "99") (name "unconnected-(U5-1A7-Pad38)") (class "Default")
      (node (ref "U5") (pin "38") (pinfunction "1A7_38") (pintype "passive"))
    )
    (net (code "100") (name "unconnected-(U5-1A8-Pad37)") (class "Default")
      (node (ref "U5") (pin "37") (pinfunction "1A8_37") (pintype "passive"))
    )
    (net (code "101") (name "unconnected-(U5-1B2-Pad3)") (class "Default")
      (node (ref "U5") (pin "3") (pinfunction "1B2_3") (pintype "passive"))
    )
    (net (code "102") (name "unconnected-(U5-1B3-Pad5)") (class "Default")
      (node (ref "U5") (pin "5") (pinfunction "1B3_5") (pintype "passive"))
    )
    (net (code "103") (name "unconnected-(U5-1B4-Pad6)") (class "Default")
      (node (ref "U5") (pin "6") (pinfunction "1B4_6") (pintype "passive"))
    )
    (net (code "104") (name "unconnected-(U5-1B5-Pad8)") (class "Default")
      (node (ref "U5") (pin "8") (pinfunction "1B5_8") (pintype "passive"))
    )
    (net (code "105") (name "unconnected-(U5-1B6-Pad9)") (class "Default")
      (node (ref "U5") (pin "9") (pinfunction "1B6_9") (pintype "passive"))
    )
    (net (code "106") (name "unconnected-(U5-1B7-Pad11)") (class "Default")
      (node (ref "U5") (pin "11") (pinfunction "1B7_11") (pintype "passive"))
    )
    (net (code "107") (name "unconnected-(U5-1B8-Pad12)") (class "Default")
      (node (ref "U5") (pin "12") (pinfunction "1B8_12") (pintype "passive"))
    )
    (net (code "108") (name "unconnected-(U5-2A2-Pad35)") (class "Default")
      (node (ref "U5") (pin "35") (pinfunction "2A2_35") (pintype "passive"))
    )
    (net (code "109") (name "unconnected-(U5-2A3-Pad33)") (class "Default")
      (node (ref "U5") (pin "33") (pinfunction "2A3_33") (pintype "passive"))
    )
    (net (code "110") (name "unconnected-(U5-2A4-Pad32)") (class "Default")
      (node (ref "U5") (pin "32") (pinfunction "2A4_32") (pintype "passive"))
    )
    (net (code "111") (name "unconnected-(U5-2A5-Pad30)") (class "Default")
      (node (ref "U5") (pin "30") (pinfunction "2A5_30") (pintype "passive"))
    )
    (net (code "112") (name "unconnected-(U5-2A6-Pad29)") (class "Default")
      (node (ref "U5") (pin "29") (pinfunction "2A6_29") (pintype "passive"))
    )
    (net (code "113") (name "unconnected-(U5-2A7-Pad27)") (class "Default")
      (node (ref "U5") (pin "27") (pinfunction "2A7_27") (pintype "passive"))
    )
    (net (code "114") (name "unconnected-(U5-2A8-Pad26)") (class "Default")
      (node (ref "U5") (pin "26") (pinfunction "2A8_26") (pintype "passive"))
    )
    (net (code "115") (name "unconnected-(U5-2B2-Pad14)") (class "Default")
      (node (ref "U5") (pin "14") (pinfunction "2B2_14") (pintype "passive"))
    )
    (net (code "116") (name "unconnected-(U5-2B3-Pad16)") (class "Default")
      (node (ref "U5") (pin "16") (pinfunction "2B3_16") (pintype "passive"))
    )
    (net (code "117") (name "unconnected-(U5-2B4-Pad17)") (class "Default")
      (node (ref "U5") (pin "17") (pinfunction "2B4_17") (pintype "passive"))
    )
    (net (code "118") (name "unconnected-(U5-2B5-Pad19)") (class "Default")
      (node (ref "U5") (pin "19") (pinfunction "2B5_19") (pintype "passive"))
    )
    (net (code "119") (name "unconnected-(U5-2B6-Pad20)") (class "Default")
      (node (ref "U5") (pin "20") (pinfunction "2B6_20") (pintype "passive"))
    )
    (net (code "120") (name "unconnected-(U5-2B7-Pad22)") (class "Default")
      (node (ref "U5") (pin "22") (pinfunction "2B7_22") (pintype "passive"))
    )
    (net (code "121") (name "unconnected-(U5-2B8-Pad23)") (class "Default")
      (node (ref "U5") (pin "23") (pinfunction "2B8_23") (pintype "passive"))
    )
  )
)
